# APRS_board_R2.net
KiCad netlist of a schematic drawn in EAGLE
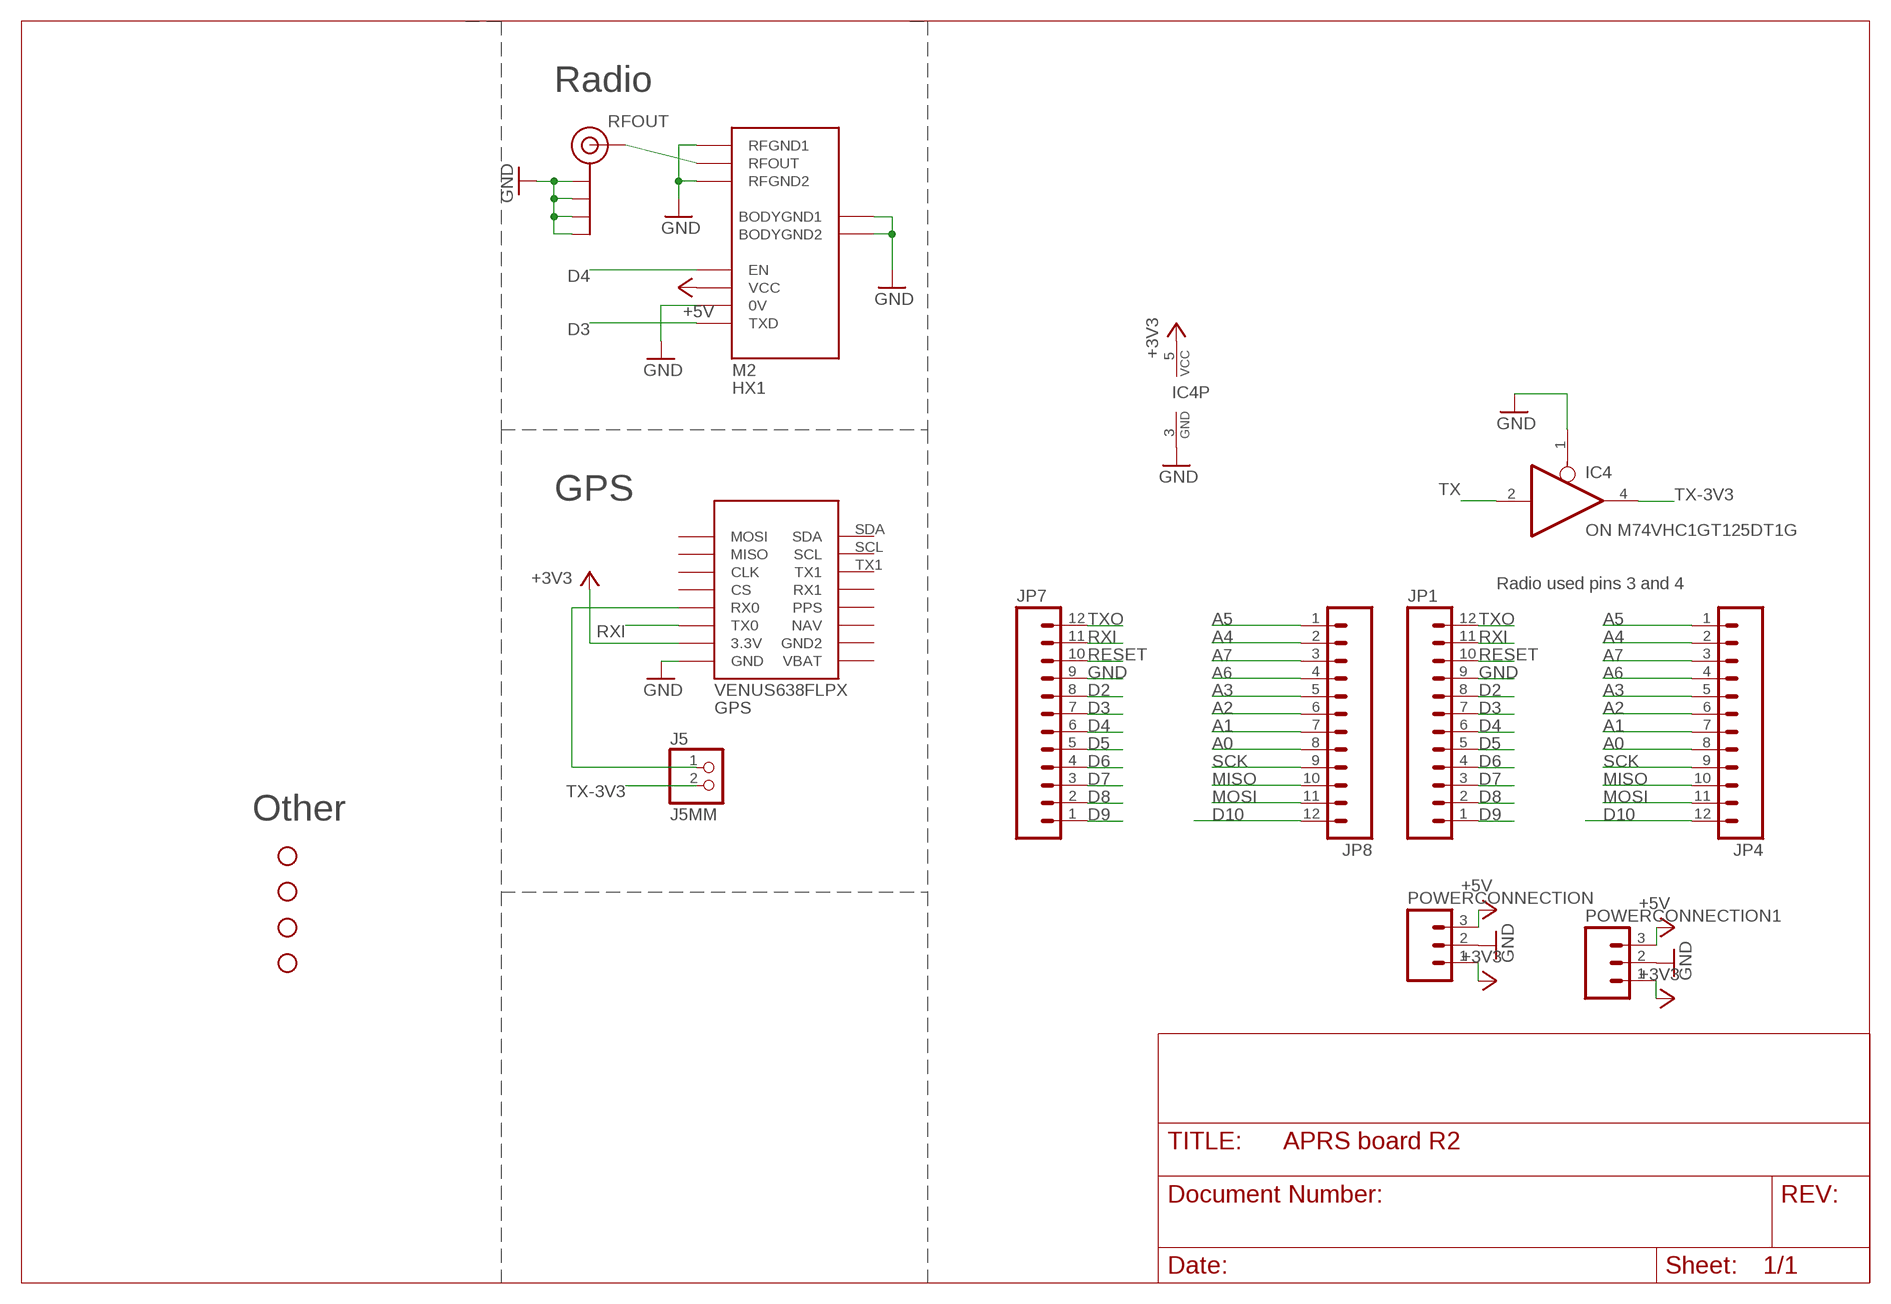
[diagram p0: schematic, sheet 1]

(export (version "E")
  (design (tool "Eeschema 10.0.6"))
  (components
    (comp (ref "GPS")
      (value "VENUS638FLPX")
      (footprint "eagle-import:VENUS638FLPX")
      (libsource (lib "eagle-import") (part "VENUS638FLPX"))
    )
    (comp (ref "IC4")
      (value "ON M74VHC1GT125DT1G")
      (footprint "eagle-import:SOT23-5")
      (libsource (lib "eagle-import") (part "741G125DBVAHC"))
    )
    (comp (ref "J$1")
      (value "SMA_EDGE")
      (footprint "eagle-import:SMA-EDGE")
      (libsource (lib "eagle-import") (part "SMA_EDGE"))
    )
    (comp (ref "J5")
      (value "J5MM")
      (footprint "eagle-import:1X02")
      (libsource (lib "eagle-import") (part "PINHD-1X2"))
    )
    (comp (ref "JP1")
      (value "M12PTH")
      (footprint "eagle-import:1X12")
      (libsource (lib "eagle-import") (part "M12PTH"))
    )
    (comp (ref "JP4")
      (value "M12PTH")
      (footprint "eagle-import:1X12")
      (libsource (lib "eagle-import") (part "M12PTH"))
    )
    (comp (ref "JP7")
      (value "M12PTH")
      (footprint "eagle-import:1X12")
      (libsource (lib "eagle-import") (part "M12PTH"))
    )
    (comp (ref "JP8")
      (value "M12PTH")
      (footprint "eagle-import:1X12")
      (libsource (lib "eagle-import") (part "M12PTH"))
    )
    (comp (ref "M2")
      (value "HX1")
      (footprint "eagle-import:HX1")
      (libsource (lib "eagle-import") (part "HX1"))
    )
    (comp (ref "POWERCONNECTION")
      (value "M03PTH")
      (footprint "eagle-import:1X03")
      (libsource (lib "eagle-import") (part "M03PTH"))
    )
    (comp (ref "POWERCONNECTION1")
      (value "M03PTH")
      (footprint "eagle-import:1X03")
      (libsource (lib "eagle-import") (part "M03PTH"))
    )
    (comp (ref "STANDOFF1")
      (value "STAND-OFF")
      (footprint "eagle-import:STAND-OFF")
      (libsource (lib "eagle-import") (part "STAND-OFF"))
    )
    (comp (ref "STANDOFF2")
      (value "STAND-OFF")
      (footprint "eagle-import:STAND-OFF")
      (libsource (lib "eagle-import") (part "STAND-OFF"))
    )
    (comp (ref "STANDOFF3")
      (value "STAND-OFF")
      (footprint "eagle-import:STAND-OFF")
      (libsource (lib "eagle-import") (part "STAND-OFF"))
    )
    (comp (ref "STANDOFF4")
      (value "STAND-OFF")
      (footprint "eagle-import:STAND-OFF")
      (libsource (lib "eagle-import") (part "STAND-OFF"))
    )
  )
  (nets
    (net (code "1") (name "+3V3") (class "Default")
      (node (ref "GPS") (pin "3.3V") (pinfunction "3.3V_3.3V") (pintype "bidirectional"))
      (node (ref "IC4") (pin "5") (pinfunction "VCC_5") (pintype "power_in"))
      (node (ref "POWERCONNECTION") (pin "1") (pinfunction "1_1") (pintype "passive"))
      (node (ref "POWERCONNECTION1") (pin "1") (pinfunction "1_1") (pintype "passive"))
    )
    (net (code "2") (name "+5V") (class "Default")
      (node (ref "M2") (pin "VCC") (pinfunction "VCC_VCC") (pintype "bidirectional"))
      (node (ref "POWERCONNECTION") (pin "3") (pinfunction "3_3") (pintype "passive"))
      (node (ref "POWERCONNECTION1") (pin "3") (pinfunction "3_3") (pintype "passive"))
    )
    (net (code "3") (name "/A0") (class "Default")
      (node (ref "JP4") (pin "8") (pinfunction "8_8") (pintype "passive"))
      (node (ref "JP8") (pin "8") (pinfunction "8_8") (pintype "passive"))
    )
    (net (code "4") (name "/A1") (class "Default")
      (node (ref "JP4") (pin "7") (pinfunction "7_7") (pintype "passive"))
      (node (ref "JP8") (pin "7") (pinfunction "7_7") (pintype "passive"))
    )
    (net (code "5") (name "/A2") (class "Default")
      (node (ref "JP4") (pin "6") (pinfunction "6_6") (pintype "passive"))
      (node (ref "JP8") (pin "6") (pinfunction "6_6") (pintype "passive"))
    )
    (net (code "6") (name "/A3") (class "Default")
      (node (ref "JP4") (pin "5") (pinfunction "5_5") (pintype "passive"))
      (node (ref "JP8") (pin "5") (pinfunction "5_5") (pintype "passive"))
    )
    (net (code "7") (name "/A4") (class "Default")
      (node (ref "JP4") (pin "2") (pinfunction "2_2") (pintype "passive"))
      (node (ref "JP8") (pin "2") (pinfunction "2_2") (pintype "passive"))
    )
    (net (code "8") (name "/A5") (class "Default")
      (node (ref "JP4") (pin "1") (pinfunction "1_1") (pintype "passive"))
      (node (ref "JP8") (pin "1") (pinfunction "1_1") (pintype "passive"))
    )
    (net (code "9") (name "/A6") (class "Default")
      (node (ref "JP4") (pin "4") (pinfunction "4_4") (pintype "passive"))
      (node (ref "JP8") (pin "4") (pinfunction "4_4") (pintype "passive"))
    )
    (net (code "10") (name "/A7") (class "Default")
      (node (ref "JP4") (pin "3") (pinfunction "3_3") (pintype "passive"))
      (node (ref "JP8") (pin "3") (pinfunction "3_3") (pintype "passive"))
    )
    (net (code "11") (name "/D2") (class "Default")
      (node (ref "JP1") (pin "8") (pinfunction "8_8") (pintype "passive"))
      (node (ref "JP7") (pin "8") (pinfunction "8_8") (pintype "passive"))
    )
    (net (code "12") (name "/D3") (class "Default")
      (node (ref "JP1") (pin "7") (pinfunction "7_7") (pintype "passive"))
      (node (ref "JP7") (pin "7") (pinfunction "7_7") (pintype "passive"))
      (node (ref "M2") (pin "TXD") (pinfunction "TXD_TXD") (pintype "bidirectional"))
    )
    (net (code "13") (name "/D4") (class "Default")
      (node (ref "JP1") (pin "6") (pinfunction "6_6") (pintype "passive"))
      (node (ref "JP7") (pin "6") (pinfunction "6_6") (pintype "passive"))
      (node (ref "M2") (pin "EN") (pinfunction "EN_EN") (pintype "bidirectional"))
    )
    (net (code "14") (name "/D5") (class "Default")
      (node (ref "JP1") (pin "5") (pinfunction "5_5") (pintype "passive"))
      (node (ref "JP7") (pin "5") (pinfunction "5_5") (pintype "passive"))
    )
    (net (code "15") (name "/D6") (class "Default")
      (node (ref "JP1") (pin "4") (pinfunction "4_4") (pintype "passive"))
      (node (ref "JP7") (pin "4") (pinfunction "4_4") (pintype "passive"))
    )
    (net (code "16") (name "/D7") (class "Default")
      (node (ref "JP1") (pin "3") (pinfunction "3_3") (pintype "passive"))
      (node (ref "JP7") (pin "3") (pinfunction "3_3") (pintype "passive"))
    )
    (net (code "17") (name "/D8") (class "Default")
      (node (ref "JP1") (pin "2") (pinfunction "2_2") (pintype "passive"))
      (node (ref "JP7") (pin "2") (pinfunction "2_2") (pintype "passive"))
    )
    (net (code "18") (name "/D9") (class "Default")
      (node (ref "JP1") (pin "1") (pinfunction "1_1") (pintype "passive"))
      (node (ref "JP7") (pin "1") (pinfunction "1_1") (pintype "passive"))
    )
    (net (code "19") (name "/D10") (class "Default")
      (node (ref "JP4") (pin "12") (pinfunction "12_12") (pintype "passive"))
      (node (ref "JP8") (pin "12") (pinfunction "12_12") (pintype "passive"))
    )
    (net (code "20") (name "/MISO") (class "Default")
      (node (ref "JP4") (pin "10") (pinfunction "10_10") (pintype "passive"))
      (node (ref "JP8") (pin "10") (pinfunction "10_10") (pintype "passive"))
    )
    (net (code "21") (name "/MOSI") (class "Default")
      (node (ref "JP4") (pin "11") (pinfunction "11_11") (pintype "passive"))
      (node (ref "JP8") (pin "11") (pinfunction "11_11") (pintype "passive"))
    )
    (net (code "22") (name "/RESET") (class "Default")
      (node (ref "JP1") (pin "10") (pinfunction "10_10") (pintype "passive"))
      (node (ref "JP7") (pin "10") (pinfunction "10_10") (pintype "passive"))
    )
    (net (code "23") (name "/RFOUT") (class "Default")
      (node (ref "J$1") (pin "SIG") (pinfunction "SIGNAL_SIG") (pintype "bidirectional"))
      (node (ref "M2") (pin "RFOUT") (pinfunction "RFOUT_RFOUT") (pintype "bidirectional"))
    )
    (net (code "24") (name "/RXI") (class "Default")
      (node (ref "GPS") (pin "TX0") (pinfunction "TX0_TX0") (pintype "bidirectional"))
      (node (ref "JP1") (pin "11") (pinfunction "11_11") (pintype "passive"))
      (node (ref "JP7") (pin "11") (pinfunction "11_11") (pintype "passive"))
    )
    (net (code "25") (name "/SCK") (class "Default")
      (node (ref "JP4") (pin "9") (pinfunction "9_9") (pintype "passive"))
      (node (ref "JP8") (pin "9") (pinfunction "9_9") (pintype "passive"))
    )
    (net (code "26") (name "/TX") (class "Default")
      (node (ref "IC4") (pin "2") (pinfunction "I_2") (pintype "input"))
    )
    (net (code "27") (name "/TX-3V3") (class "Default")
      (node (ref "IC4") (pin "4") (pinfunction "O_4") (pintype "tri_state"))
      (node (ref "J5") (pin "2") (pinfunction "2_2") (pintype "passive"))
    )
    (net (code "28") (name "/TXO") (class "Default")
      (node (ref "JP1") (pin "12") (pinfunction "12_12") (pintype "passive"))
      (node (ref "JP7") (pin "12") (pinfunction "12_12") (pintype "passive"))
    )
    (net (code "29") (name "GND") (class "Default")
      (node (ref "GPS") (pin "GND") (pinfunction "GND_GND") (pintype "bidirectional"))
      (node (ref "IC4") (pin "1") (pinfunction "OE_1") (pintype "input"))
      (node (ref "IC4") (pin "3") (pinfunction "GND_3") (pintype "power_in"))
      (node (ref "J$1") (pin "GND@0") (pinfunction "GND_GND@0") (pintype "bidirectional"))
      (node (ref "J$1") (pin "GND@1") (pinfunction "GND_GND@1") (pintype "bidirectional"))
      (node (ref "J$1") (pin "GND@2") (pinfunction "GND_GND@2") (pintype "bidirectional"))
      (node (ref "J$1") (pin "GND@3") (pinfunction "GND_GND@3") (pintype "bidirectional"))
      (node (ref "JP1") (pin "9") (pinfunction "9_9") (pintype "passive"))
      (node (ref "JP7") (pin "9") (pinfunction "9_9") (pintype "passive"))
      (node (ref "M2") (pin "0V") (pinfunction "0V_0V") (pintype "bidirectional"))
      (node (ref "M2") (pin "BODYGND1") (pinfunction "BODYGND1_BODYGND1") (pintype "bidirectional"))
      (node (ref "M2") (pin "BODYGND2") (pinfunction "BODYGND2_BODYGND2") (pintype "bidirectional"))
      (node (ref "M2") (pin "RFGND1") (pinfunction "RFGND1_RFGND1") (pintype "bidirectional"))
      (node (ref "M2") (pin "RFGND2") (pinfunction "RFGND2_RFGND2") (pintype "bidirectional"))
      (node (ref "POWERCONNECTION") (pin "2") (pinfunction "2_2") (pintype "passive"))
      (node (ref "POWERCONNECTION1") (pin "2") (pinfunction "2_2") (pintype "passive"))
    )
    (net (code "30") (name "Net-(GPS-PadRX0)") (class "Default")
      (node (ref "GPS") (pin "RX0") (pinfunction "RX0_RX0") (pintype "bidirectional"))
      (node (ref "J5") (pin "1") (pinfunction "1_1") (pintype "passive"))
    )
    (net (code "31") (name "unconnected-(GPS-PadCLK)") (class "Default")
      (node (ref "GPS") (pin "CLK") (pinfunction "CLK_CLK") (pintype "bidirectional"))
    )
    (net (code "32") (name "unconnected-(GPS-PadCS)") (class "Default")
      (node (ref "GPS") (pin "CS") (pinfunction "CS_CS") (pintype "bidirectional"))
    )
    (net (code "33") (name "unconnected-(GPS-PadGND2)") (class "Default")
      (node (ref "GPS") (pin "GND2") (pinfunction "GND2_GND2") (pintype "bidirectional"))
    )
    (net (code "34") (name "unconnected-(GPS-PadMISO)") (class "Default")
      (node (ref "GPS") (pin "MISO") (pinfunction "MISO_MISO") (pintype "bidirectional"))
    )
    (net (code "35") (name "unconnected-(GPS-PadMOSI)") (class "Default")
      (node (ref "GPS") (pin "MOSI") (pinfunction "MOSI_MOSI") (pintype "bidirectional"))
    )
    (net (code "36") (name "unconnected-(GPS-PadNAV)") (class "Default")
      (node (ref "GPS") (pin "NAV") (pinfunction "NAV_NAV") (pintype "bidirectional"))
    )
    (net (code "37") (name "unconnected-(GPS-PadPPS)") (class "Default")
      (node (ref "GPS") (pin "PPS") (pinfunction "PPS_PPS") (pintype "bidirectional"))
    )
    (net (code "38") (name "unconnected-(GPS-PadRX1)") (class "Default")
      (node (ref "GPS") (pin "RX1") (pinfunction "RX1_RX1") (pintype "bidirectional"))
    )
    (net (code "39") (name "unconnected-(GPS-PadSCL)") (class "Default")
      (node (ref "GPS") (pin "SCL") (pinfunction "SCL_SCL") (pintype "bidirectional"))
    )
    (net (code "40") (name "unconnected-(GPS-PadSDA)") (class "Default")
      (node (ref "GPS") (pin "SDA") (pinfunction "SDA_SDA") (pintype "bidirectional"))
    )
    (net (code "41") (name "unconnected-(GPS-PadTX1)") (class "Default")
      (node (ref "GPS") (pin "TX1") (pinfunction "TX1_TX1") (pintype "bidirectional"))
    )
    (net (code "42") (name "unconnected-(GPS-PadVBAT)") (class "Default")
      (node (ref "GPS") (pin "VBAT") (pinfunction "VBAT_VBAT") (pintype "bidirectional"))
    )
  )
)
